# 9VPart.net
KiCad netlist of a schematic drawn in EAGLE
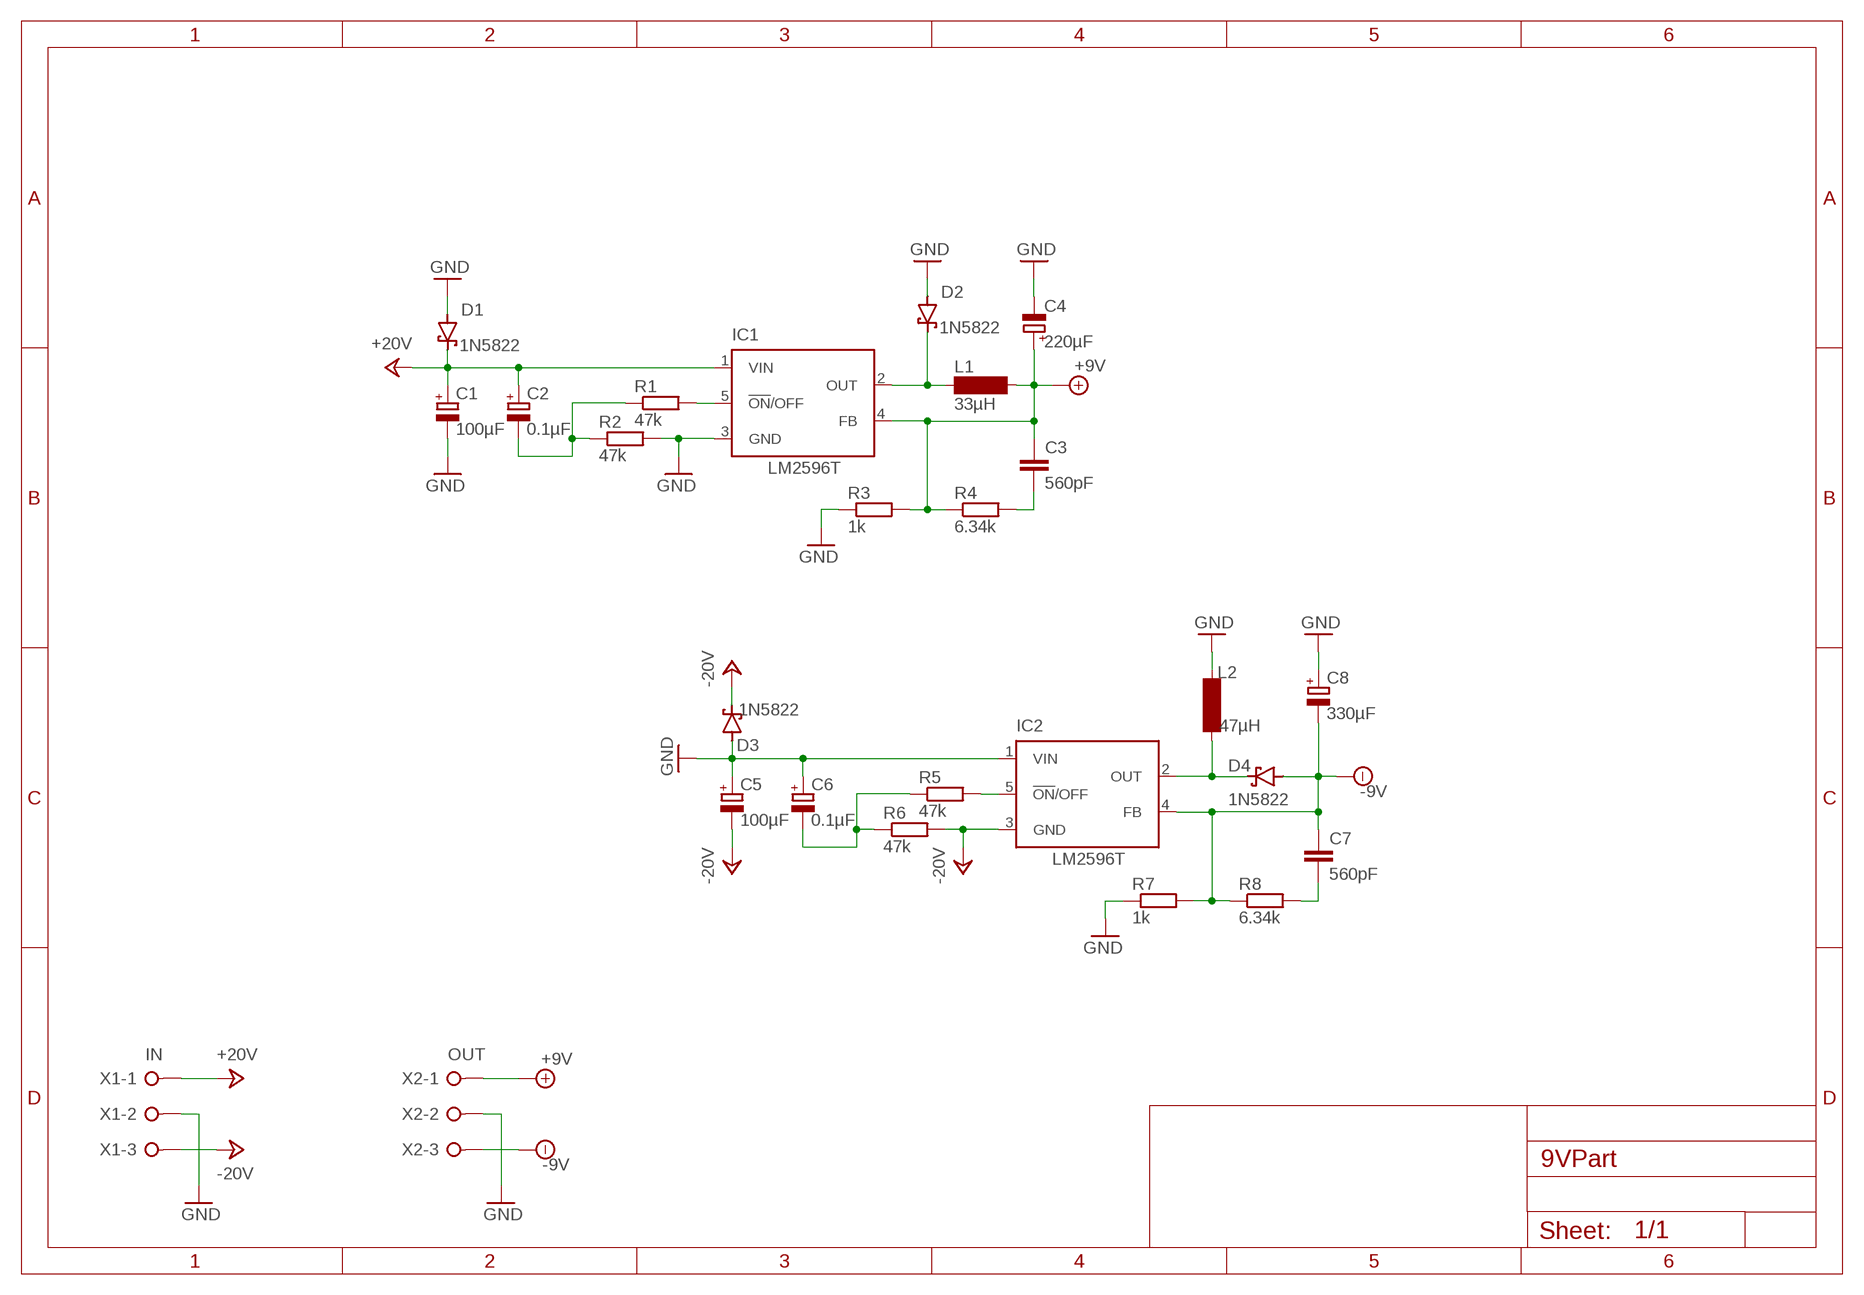
[diagram p0: schematic, sheet 1]

(export (version "E")
  (design (tool "Eeschema 10.0.6"))
  (components
    (comp (ref "C1")
      (value "100µF")
      (footprint "eagle-import:E2,5-6")
      (libsource (lib "eagle-import") (part "CPOL-EUE2.5-6"))
    )
    (comp (ref "C2")
      (value "0.1µF")
      (footprint "eagle-import:E1,8-4")
      (libsource (lib "eagle-import") (part "CPOL-EUE1.8-4"))
    )
    (comp (ref "C3")
      (value "560pF")
      (footprint "eagle-import:C050-024X044")
      (libsource (lib "eagle-import") (part "C-EU050-024X044"))
    )
    (comp (ref "C4")
      (value "220µF")
      (footprint "eagle-import:E3,5-8")
      (libsource (lib "eagle-import") (part "CPOL-EUE3.5-8"))
    )
    (comp (ref "C5")
      (value "100µF")
      (footprint "eagle-import:E2,5-6")
      (libsource (lib "eagle-import") (part "CPOL-EUE2.5-6"))
    )
    (comp (ref "C6")
      (value "0.1µF")
      (footprint "eagle-import:E1,8-4")
      (libsource (lib "eagle-import") (part "CPOL-EUE1.8-4"))
    )
    (comp (ref "C7")
      (value "560pF")
      (footprint "eagle-import:C050-024X044")
      (libsource (lib "eagle-import") (part "C-EU050-024X044"))
    )
    (comp (ref "C8")
      (value "330µF")
      (footprint "eagle-import:E3,5-8")
      (libsource (lib "eagle-import") (part "CPOL-EUE3.5-8"))
    )
    (comp (ref "D1")
      (value "1N5822")
      (footprint "eagle-import:C4111-15")
      (libsource (lib "eagle-import") (part "SCHOTTKY-DIODEC4111-15"))
    )
    (comp (ref "D2")
      (value "1N5822")
      (footprint "eagle-import:C4111-15")
      (libsource (lib "eagle-import") (part "SCHOTTKY-DIODEC4111-15"))
    )
    (comp (ref "D3")
      (value "1N5822")
      (footprint "eagle-import:C4111-15")
      (libsource (lib "eagle-import") (part "SCHOTTKY-DIODEC4111-15"))
    )
    (comp (ref "D4")
      (value "1N5822")
      (footprint "eagle-import:C4111-15")
      (libsource (lib "eagle-import") (part "SCHOTTKY-DIODEC4111-15"))
    )
    (comp (ref "IC1")
      (value "LM2596T")
      (footprint "eagle-import:T05D")
      (fields (field (name "MPN") "LM2596T-ADJ/LF02"))
      (libsource (lib "eagle-import") (part "LM2596T"))
    )
    (comp (ref "IC2")
      (value "LM2596T")
      (footprint "eagle-import:T05D")
      (fields (field (name "MPN") "LM2596T-ADJ/LF02"))
      (libsource (lib "eagle-import") (part "LM2596T"))
    )
    (comp (ref "L1")
      (value "33µH")
      (footprint "eagle-import:SD12-680")
      (fields (field (name "MF") "BUSSMANN") (field (name "MPN") "SD12-680"))
      (libsource (lib "eagle-import") (part "SD12-680"))
    )
    (comp (ref "L2")
      (value "47µH")
      (footprint "eagle-import:SD12-680")
      (fields (field (name "MF") "BUSSMANN") (field (name "MPN") "SD12-680"))
      (libsource (lib "eagle-import") (part "SD12-680"))
    )
    (comp (ref "R1")
      (value "47k")
      (footprint "eagle-import:0207_10")
      (libsource (lib "eagle-import") (part "R-EU_0207/10"))
    )
    (comp (ref "R2")
      (value "47k")
      (footprint "eagle-import:0207_10")
      (libsource (lib "eagle-import") (part "R-EU_0207/10"))
    )
    (comp (ref "R3")
      (value "1k")
      (footprint "eagle-import:0207_10")
      (libsource (lib "eagle-import") (part "R-EU_0207/10"))
    )
    (comp (ref "R4")
      (value "6.34k")
      (footprint "eagle-import:0207_10")
      (libsource (lib "eagle-import") (part "R-EU_0207/10"))
    )
    (comp (ref "R5")
      (value "47k")
      (footprint "eagle-import:0207_10")
      (libsource (lib "eagle-import") (part "R-EU_0207/10"))
    )
    (comp (ref "R6")
      (value "47k")
      (footprint "eagle-import:0207_10")
      (libsource (lib "eagle-import") (part "R-EU_0207/10"))
    )
    (comp (ref "R7")
      (value "1k")
      (footprint "eagle-import:0207_10")
      (libsource (lib "eagle-import") (part "R-EU_0207/10"))
    )
    (comp (ref "R8")
      (value "6.34k")
      (footprint "eagle-import:0207_10")
      (libsource (lib "eagle-import") (part "R-EU_0207/10"))
    )
    (comp (ref "X1")
      (value "IN")
      (footprint "eagle-import:W237-133")
      (libsource (lib "eagle-import") (part "W237-03P"))
    )
    (comp (ref "X2")
      (value "OUT")
      (footprint "eagle-import:W237-133")
      (libsource (lib "eagle-import") (part "W237-03P"))
    )
  )
  (nets
    (net (code "1") (name "+9V") (class "Default")
      (node (ref "C3") (pin "1") (pinfunction "1_1") (pintype "passive"))
      (node (ref "C4") (pin "+") (pinfunction "+_+") (pintype "passive"))
      (node (ref "IC1") (pin "4") (pinfunction "FB_4") (pintype "input"))
      (node (ref "L1") (pin "2") (pinfunction "2_2") (pintype "passive"))
      (node (ref "R3") (pin "2") (pinfunction "2_2") (pintype "passive"))
      (node (ref "R4") (pin "1") (pinfunction "1_1") (pintype "passive"))
      (node (ref "X2") (pin "1") (pinfunction "KL_1") (pintype "passive"))
    )
    (net (code "2") (name "+20V") (class "Default")
      (node (ref "C1") (pin "+") (pinfunction "+_+") (pintype "passive"))
      (node (ref "C2") (pin "+") (pinfunction "+_+") (pintype "passive"))
      (node (ref "D1") (pin "C") (pinfunction "C_C") (pintype "passive"))
      (node (ref "IC1") (pin "1") (pinfunction "VIN_1") (pintype "input"))
      (node (ref "X1") (pin "1") (pinfunction "KL_1") (pintype "passive"))
    )
    (net (code "3") (name "-9V") (class "Default")
      (node (ref "C7") (pin "1") (pinfunction "1_1") (pintype "passive"))
      (node (ref "C8") (pin "-") (pinfunction "-_-") (pintype "passive"))
      (node (ref "D4") (pin "A") (pinfunction "A_A") (pintype "passive"))
      (node (ref "IC2") (pin "4") (pinfunction "FB_4") (pintype "input"))
      (node (ref "R7") (pin "2") (pinfunction "2_2") (pintype "passive"))
      (node (ref "R8") (pin "1") (pinfunction "1_1") (pintype "passive"))
      (node (ref "X2") (pin "3") (pinfunction "KL_3") (pintype "passive"))
    )
    (net (code "4") (name "-20V") (class "Default")
      (node (ref "C5") (pin "-") (pinfunction "-_-") (pintype "passive"))
      (node (ref "D3") (pin "C") (pinfunction "C_C") (pintype "passive"))
      (node (ref "IC2") (pin "3") (pinfunction "GND_3") (pintype "power_in"))
      (node (ref "R6") (pin "2") (pinfunction "2_2") (pintype "passive"))
      (node (ref "X1") (pin "3") (pinfunction "KL_3") (pintype "passive"))
    )
    (net (code "5") (name "GND") (class "Default")
      (node (ref "C1") (pin "-") (pinfunction "-_-") (pintype "passive"))
      (node (ref "C4") (pin "-") (pinfunction "-_-") (pintype "passive"))
      (node (ref "C5") (pin "+") (pinfunction "+_+") (pintype "passive"))
      (node (ref "C6") (pin "+") (pinfunction "+_+") (pintype "passive"))
      (node (ref "C8") (pin "+") (pinfunction "+_+") (pintype "passive"))
      (node (ref "D1") (pin "A") (pinfunction "A_A") (pintype "passive"))
      (node (ref "D2") (pin "A") (pinfunction "A_A") (pintype "passive"))
      (node (ref "D3") (pin "A") (pinfunction "A_A") (pintype "passive"))
      (node (ref "IC1") (pin "3") (pinfunction "GND_3") (pintype "power_in"))
      (node (ref "IC2") (pin "1") (pinfunction "VIN_1") (pintype "input"))
      (node (ref "L2") (pin "2") (pinfunction "2_2") (pintype "passive"))
      (node (ref "R2") (pin "2") (pinfunction "2_2") (pintype "passive"))
      (node (ref "R3") (pin "1") (pinfunction "1_1") (pintype "passive"))
      (node (ref "R7") (pin "1") (pinfunction "1_1") (pintype "passive"))
      (node (ref "X1") (pin "2") (pinfunction "KL_2") (pintype "passive"))
      (node (ref "X2") (pin "2") (pinfunction "KL_2") (pintype "passive"))
    )
    (net (code "6") (name "Net-(C2-Pad-)") (class "Default")
      (node (ref "C2") (pin "-") (pinfunction "-_-") (pintype "passive"))
      (node (ref "R1") (pin "1") (pinfunction "1_1") (pintype "passive"))
      (node (ref "R2") (pin "1") (pinfunction "1_1") (pintype "passive"))
    )
    (net (code "7") (name "Net-(C3-Pad2)") (class "Default")
      (node (ref "C3") (pin "2") (pinfunction "2_2") (pintype "passive"))
      (node (ref "R4") (pin "2") (pinfunction "2_2") (pintype "passive"))
    )
    (net (code "8") (name "Net-(C6-Pad-)") (class "Default")
      (node (ref "C6") (pin "-") (pinfunction "-_-") (pintype "passive"))
      (node (ref "R5") (pin "1") (pinfunction "1_1") (pintype "passive"))
      (node (ref "R6") (pin "1") (pinfunction "1_1") (pintype "passive"))
    )
    (net (code "9") (name "Net-(C7-Pad2)") (class "Default")
      (node (ref "C7") (pin "2") (pinfunction "2_2") (pintype "passive"))
      (node (ref "R8") (pin "2") (pinfunction "2_2") (pintype "passive"))
    )
    (net (code "10") (name "Net-(IC1-OUT)") (class "Default")
      (node (ref "D2") (pin "C") (pinfunction "C_C") (pintype "passive"))
      (node (ref "IC1") (pin "2") (pinfunction "OUT_2") (pintype "output"))
      (node (ref "L1") (pin "1") (pinfunction "1_1") (pintype "passive"))
    )
    (net (code "11") (name "Net-(IC1-~{ON}{slash}OFF)") (class "Default")
      (node (ref "IC1") (pin "5") (pinfunction "~{ON}/OFF_5") (pintype "input"))
      (node (ref "R1") (pin "2") (pinfunction "2_2") (pintype "passive"))
    )
    (net (code "12") (name "Net-(IC2-OUT)") (class "Default")
      (node (ref "D4") (pin "C") (pinfunction "C_C") (pintype "passive"))
      (node (ref "IC2") (pin "2") (pinfunction "OUT_2") (pintype "output"))
      (node (ref "L2") (pin "1") (pinfunction "1_1") (pintype "passive"))
    )
    (net (code "13") (name "Net-(IC2-~{ON}{slash}OFF)") (class "Default")
      (node (ref "IC2") (pin "5") (pinfunction "~{ON}/OFF_5") (pintype "input"))
      (node (ref "R5") (pin "2") (pinfunction "2_2") (pintype "passive"))
    )
  )
)
